# 30_SOC.net
KiCad netlist of a schematic drawn in Altium Designer
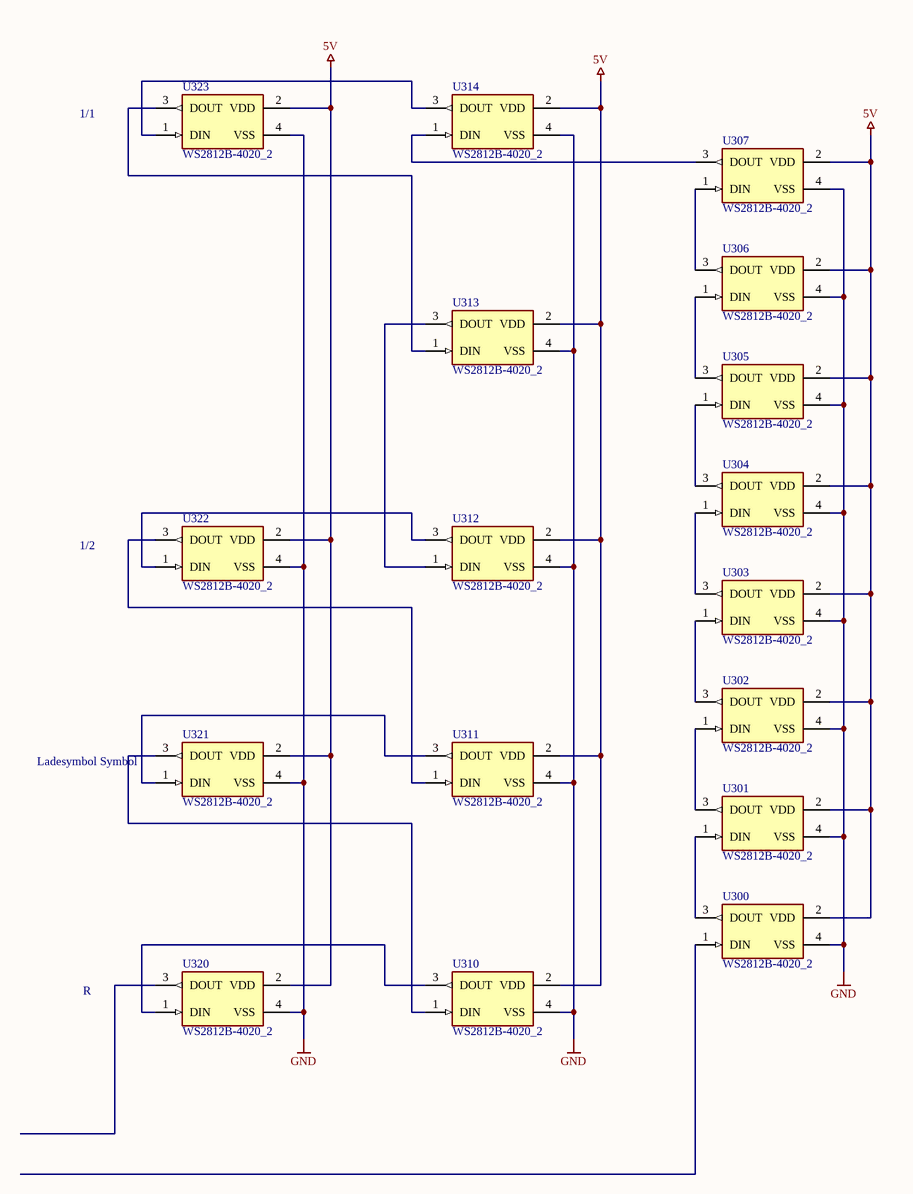
[diagram p0: 30_SOC.SchDoc]

(export (version "E")
  (design (tool "Eeschema 10.0.6"))
  (components
    (comp (ref "U300")
      (value "WS2812B-4020_2")
      (footprint "LED_WS2812B-4020")
      (description "12mA RGB SMD,2x4mm Light Emitting Diodes")
      (fields (field (name "MP") "WS2812B-4020") (field (name "MF") "Worldsemi"))
      (libsource (lib "AltiumLib_MILUTIN") (part "WS2812B-4020_2"))
    )
    (comp (ref "U301")
      (value "WS2812B-4020_2")
      (footprint "LED_WS2812B-4020")
      (description "12mA RGB SMD,2x4mm Light Emitting Diodes")
      (fields (field (name "MP") "WS2812B-4020") (field (name "MF") "Worldsemi"))
      (libsource (lib "AltiumLib_MILUTIN") (part "WS2812B-4020_2"))
    )
    (comp (ref "U302")
      (value "WS2812B-4020_2")
      (footprint "LED_WS2812B-4020")
      (description "12mA RGB SMD,2x4mm Light Emitting Diodes")
      (fields (field (name "MP") "WS2812B-4020") (field (name "MF") "Worldsemi"))
      (libsource (lib "AltiumLib_MILUTIN") (part "WS2812B-4020_2"))
    )
    (comp (ref "U303")
      (value "WS2812B-4020_2")
      (footprint "LED_WS2812B-4020")
      (description "12mA RGB SMD,2x4mm Light Emitting Diodes")
      (fields (field (name "MP") "WS2812B-4020") (field (name "MF") "Worldsemi"))
      (libsource (lib "AltiumLib_MILUTIN") (part "WS2812B-4020_2"))
    )
    (comp (ref "U304")
      (value "WS2812B-4020_2")
      (footprint "LED_WS2812B-4020")
      (description "12mA RGB SMD,2x4mm Light Emitting Diodes")
      (fields (field (name "MP") "WS2812B-4020") (field (name "MF") "Worldsemi"))
      (libsource (lib "AltiumLib_MILUTIN") (part "WS2812B-4020_2"))
    )
    (comp (ref "U305")
      (value "WS2812B-4020_2")
      (footprint "LED_WS2812B-4020")
      (description "12mA RGB SMD,2x4mm Light Emitting Diodes")
      (fields (field (name "MP") "WS2812B-4020") (field (name "MF") "Worldsemi"))
      (libsource (lib "AltiumLib_MILUTIN") (part "WS2812B-4020_2"))
    )
    (comp (ref "U306")
      (value "WS2812B-4020_2")
      (footprint "LED_WS2812B-4020")
      (description "12mA RGB SMD,2x4mm Light Emitting Diodes")
      (fields (field (name "MP") "WS2812B-4020") (field (name "MF") "Worldsemi"))
      (libsource (lib "AltiumLib_MILUTIN") (part "WS2812B-4020_2"))
    )
    (comp (ref "U307")
      (value "WS2812B-4020_2")
      (footprint "LED_WS2812B-4020")
      (description "12mA RGB SMD,2x4mm Light Emitting Diodes")
      (fields (field (name "MP") "WS2812B-4020") (field (name "MF") "Worldsemi"))
      (libsource (lib "AltiumLib_MILUTIN") (part "WS2812B-4020_2"))
    )
    (comp (ref "U310")
      (value "WS2812B-4020_2")
      (footprint "LED_WS2812B-4020")
      (description "12mA RGB SMD,2x4mm Light Emitting Diodes")
      (fields (field (name "MP") "WS2812B-4020") (field (name "MF") "Worldsemi"))
      (libsource (lib "AltiumLib_MILUTIN") (part "WS2812B-4020_2"))
    )
    (comp (ref "U311")
      (value "WS2812B-4020_2")
      (footprint "LED_WS2812B-4020")
      (description "12mA RGB SMD,2x4mm Light Emitting Diodes")
      (fields (field (name "MP") "WS2812B-4020") (field (name "MF") "Worldsemi"))
      (libsource (lib "AltiumLib_MILUTIN") (part "WS2812B-4020_2"))
    )
    (comp (ref "U312")
      (value "WS2812B-4020_2")
      (footprint "LED_WS2812B-4020")
      (description "12mA RGB SMD,2x4mm Light Emitting Diodes")
      (fields (field (name "MP") "WS2812B-4020") (field (name "MF") "Worldsemi"))
      (libsource (lib "AltiumLib_MILUTIN") (part "WS2812B-4020_2"))
    )
    (comp (ref "U313")
      (value "WS2812B-4020_2")
      (footprint "LED_WS2812B-4020")
      (description "12mA RGB SMD,2x4mm Light Emitting Diodes")
      (fields (field (name "MP") "WS2812B-4020") (field (name "MF") "Worldsemi"))
      (libsource (lib "AltiumLib_MILUTIN") (part "WS2812B-4020_2"))
    )
    (comp (ref "U314")
      (value "WS2812B-4020_2")
      (footprint "LED_WS2812B-4020")
      (description "12mA RGB SMD,2x4mm Light Emitting Diodes")
      (fields (field (name "MP") "WS2812B-4020") (field (name "MF") "Worldsemi"))
      (libsource (lib "AltiumLib_MILUTIN") (part "WS2812B-4020_2"))
    )
    (comp (ref "U320")
      (value "WS2812B-4020_2")
      (footprint "LED_WS2812B-4020")
      (description "12mA RGB SMD,2x4mm Light Emitting Diodes")
      (fields (field (name "MP") "WS2812B-4020") (field (name "MF") "Worldsemi"))
      (libsource (lib "AltiumLib_MILUTIN") (part "WS2812B-4020_2"))
    )
    (comp (ref "U321")
      (value "WS2812B-4020_2")
      (footprint "LED_WS2812B-4020")
      (description "12mA RGB SMD,2x4mm Light Emitting Diodes")
      (fields (field (name "MP") "WS2812B-4020") (field (name "MF") "Worldsemi"))
      (libsource (lib "AltiumLib_MILUTIN") (part "WS2812B-4020_2"))
    )
    (comp (ref "U322")
      (value "WS2812B-4020_2")
      (footprint "LED_WS2812B-4020")
      (description "12mA RGB SMD,2x4mm Light Emitting Diodes")
      (fields (field (name "MP") "WS2812B-4020") (field (name "MF") "Worldsemi"))
      (libsource (lib "AltiumLib_MILUTIN") (part "WS2812B-4020_2"))
    )
    (comp (ref "U323")
      (value "WS2812B-4020_2")
      (footprint "LED_WS2812B-4020")
      (description "12mA RGB SMD,2x4mm Light Emitting Diodes")
      (fields (field (name "MP") "WS2812B-4020") (field (name "MF") "Worldsemi"))
      (libsource (lib "AltiumLib_MILUTIN") (part "WS2812B-4020_2"))
    )
  )
  (nets
    (net (code "1") (name "5V") (class "Default")
      (node (ref "U300") (pin "2") (pinfunction "VDD_2") (pintype "power_in"))
      (node (ref "U301") (pin "2") (pinfunction "VDD_2") (pintype "power_in"))
      (node (ref "U302") (pin "2") (pinfunction "VDD_2") (pintype "power_in"))
      (node (ref "U303") (pin "2") (pinfunction "VDD_2") (pintype "power_in"))
      (node (ref "U304") (pin "2") (pinfunction "VDD_2") (pintype "power_in"))
      (node (ref "U305") (pin "2") (pinfunction "VDD_2") (pintype "power_in"))
      (node (ref "U306") (pin "2") (pinfunction "VDD_2") (pintype "power_in"))
      (node (ref "U307") (pin "2") (pinfunction "VDD_2") (pintype "power_in"))
      (node (ref "U310") (pin "2") (pinfunction "VDD_2") (pintype "power_in"))
      (node (ref "U311") (pin "2") (pinfunction "VDD_2") (pintype "power_in"))
      (node (ref "U312") (pin "2") (pinfunction "VDD_2") (pintype "power_in"))
      (node (ref "U313") (pin "2") (pinfunction "VDD_2") (pintype "power_in"))
      (node (ref "U314") (pin "2") (pinfunction "VDD_2") (pintype "power_in"))
      (node (ref "U320") (pin "2") (pinfunction "VDD_2") (pintype "power_in"))
      (node (ref "U321") (pin "2") (pinfunction "VDD_2") (pintype "power_in"))
      (node (ref "U322") (pin "2") (pinfunction "VDD_2") (pintype "power_in"))
      (node (ref "U323") (pin "2") (pinfunction "VDD_2") (pintype "power_in"))
    )
    (net (code "2") (name "GND") (class "Default")
      (node (ref "U300") (pin "4") (pinfunction "VSS_4") (pintype "power_in"))
      (node (ref "U301") (pin "4") (pinfunction "VSS_4") (pintype "power_in"))
      (node (ref "U302") (pin "4") (pinfunction "VSS_4") (pintype "power_in"))
      (node (ref "U303") (pin "4") (pinfunction "VSS_4") (pintype "power_in"))
      (node (ref "U304") (pin "4") (pinfunction "VSS_4") (pintype "power_in"))
      (node (ref "U305") (pin "4") (pinfunction "VSS_4") (pintype "power_in"))
      (node (ref "U306") (pin "4") (pinfunction "VSS_4") (pintype "power_in"))
      (node (ref "U307") (pin "4") (pinfunction "VSS_4") (pintype "power_in"))
      (node (ref "U310") (pin "4") (pinfunction "VSS_4") (pintype "power_in"))
      (node (ref "U311") (pin "4") (pinfunction "VSS_4") (pintype "power_in"))
      (node (ref "U312") (pin "4") (pinfunction "VSS_4") (pintype "power_in"))
      (node (ref "U313") (pin "4") (pinfunction "VSS_4") (pintype "power_in"))
      (node (ref "U314") (pin "4") (pinfunction "VSS_4") (pintype "power_in"))
      (node (ref "U320") (pin "4") (pinfunction "VSS_4") (pintype "power_in"))
      (node (ref "U321") (pin "4") (pinfunction "VSS_4") (pintype "power_in"))
      (node (ref "U322") (pin "4") (pinfunction "VSS_4") (pintype "power_in"))
      (node (ref "U323") (pin "4") (pinfunction "VSS_4") (pintype "power_in"))
    )
    (net (code "3") (name "Net-(U300-DOUT)") (class "Default")
      (node (ref "U300") (pin "3") (pinfunction "DOUT_3") (pintype "output"))
      (node (ref "U301") (pin "1") (pinfunction "DIN_1") (pintype "input"))
    )
    (net (code "4") (name "Net-(U301-DOUT)") (class "Default")
      (node (ref "U301") (pin "3") (pinfunction "DOUT_3") (pintype "output"))
      (node (ref "U302") (pin "1") (pinfunction "DIN_1") (pintype "input"))
    )
    (net (code "5") (name "Net-(U302-DOUT)") (class "Default")
      (node (ref "U302") (pin "3") (pinfunction "DOUT_3") (pintype "output"))
      (node (ref "U303") (pin "1") (pinfunction "DIN_1") (pintype "input"))
    )
    (net (code "6") (name "Net-(U303-DOUT)") (class "Default")
      (node (ref "U303") (pin "3") (pinfunction "DOUT_3") (pintype "output"))
      (node (ref "U304") (pin "1") (pinfunction "DIN_1") (pintype "input"))
    )
    (net (code "7") (name "Net-(U304-DOUT)") (class "Default")
      (node (ref "U304") (pin "3") (pinfunction "DOUT_3") (pintype "output"))
      (node (ref "U305") (pin "1") (pinfunction "DIN_1") (pintype "input"))
    )
    (net (code "8") (name "Net-(U305-DOUT)") (class "Default")
      (node (ref "U305") (pin "3") (pinfunction "DOUT_3") (pintype "output"))
      (node (ref "U306") (pin "1") (pinfunction "DIN_1") (pintype "input"))
    )
    (net (code "9") (name "Net-(U306-DOUT)") (class "Default")
      (node (ref "U306") (pin "3") (pinfunction "DOUT_3") (pintype "output"))
      (node (ref "U307") (pin "1") (pinfunction "DIN_1") (pintype "input"))
    )
    (net (code "10") (name "Net-(U307-DOUT)") (class "Default")
      (node (ref "U307") (pin "3") (pinfunction "DOUT_3") (pintype "output"))
      (node (ref "U314") (pin "1") (pinfunction "DIN_1") (pintype "input"))
    )
    (net (code "11") (name "Net-(U310-DIN)") (class "Default")
      (node (ref "U310") (pin "1") (pinfunction "DIN_1") (pintype "input"))
      (node (ref "U321") (pin "3") (pinfunction "DOUT_3") (pintype "output"))
    )
    (net (code "12") (name "Net-(U310-DOUT)") (class "Default")
      (node (ref "U310") (pin "3") (pinfunction "DOUT_3") (pintype "output"))
      (node (ref "U320") (pin "1") (pinfunction "DIN_1") (pintype "input"))
    )
    (net (code "13") (name "Net-(U311-DIN)") (class "Default")
      (node (ref "U311") (pin "1") (pinfunction "DIN_1") (pintype "input"))
      (node (ref "U322") (pin "3") (pinfunction "DOUT_3") (pintype "output"))
    )
    (net (code "14") (name "Net-(U311-DOUT)") (class "Default")
      (node (ref "U311") (pin "3") (pinfunction "DOUT_3") (pintype "output"))
      (node (ref "U321") (pin "1") (pinfunction "DIN_1") (pintype "input"))
    )
    (net (code "15") (name "Net-(U312-DIN)") (class "Default")
      (node (ref "U312") (pin "1") (pinfunction "DIN_1") (pintype "input"))
      (node (ref "U313") (pin "3") (pinfunction "DOUT_3") (pintype "output"))
    )
    (net (code "16") (name "Net-(U312-DOUT)") (class "Default")
      (node (ref "U312") (pin "3") (pinfunction "DOUT_3") (pintype "output"))
      (node (ref "U322") (pin "1") (pinfunction "DIN_1") (pintype "input"))
    )
    (net (code "17") (name "Net-(U313-DIN)") (class "Default")
      (node (ref "U313") (pin "1") (pinfunction "DIN_1") (pintype "input"))
      (node (ref "U323") (pin "3") (pinfunction "DOUT_3") (pintype "output"))
    )
    (net (code "18") (name "Net-(U314-DOUT)") (class "Default")
      (node (ref "U314") (pin "3") (pinfunction "DOUT_3") (pintype "output"))
      (node (ref "U323") (pin "1") (pinfunction "DIN_1") (pintype "input"))
    )
    (net (code "19") (name "unconnected-(U300-DIN-Pad1)") (class "Default")
      (node (ref "U300") (pin "1") (pinfunction "DIN_1") (pintype "input"))
    )
    (net (code "20") (name "unconnected-(U320-DOUT-Pad3)") (class "Default")
      (node (ref "U320") (pin "3") (pinfunction "DOUT_3") (pintype "output"))
    )
  )
)
